# piZero_node_new.net
KiCad netlist of a schematic drawn in EAGLE
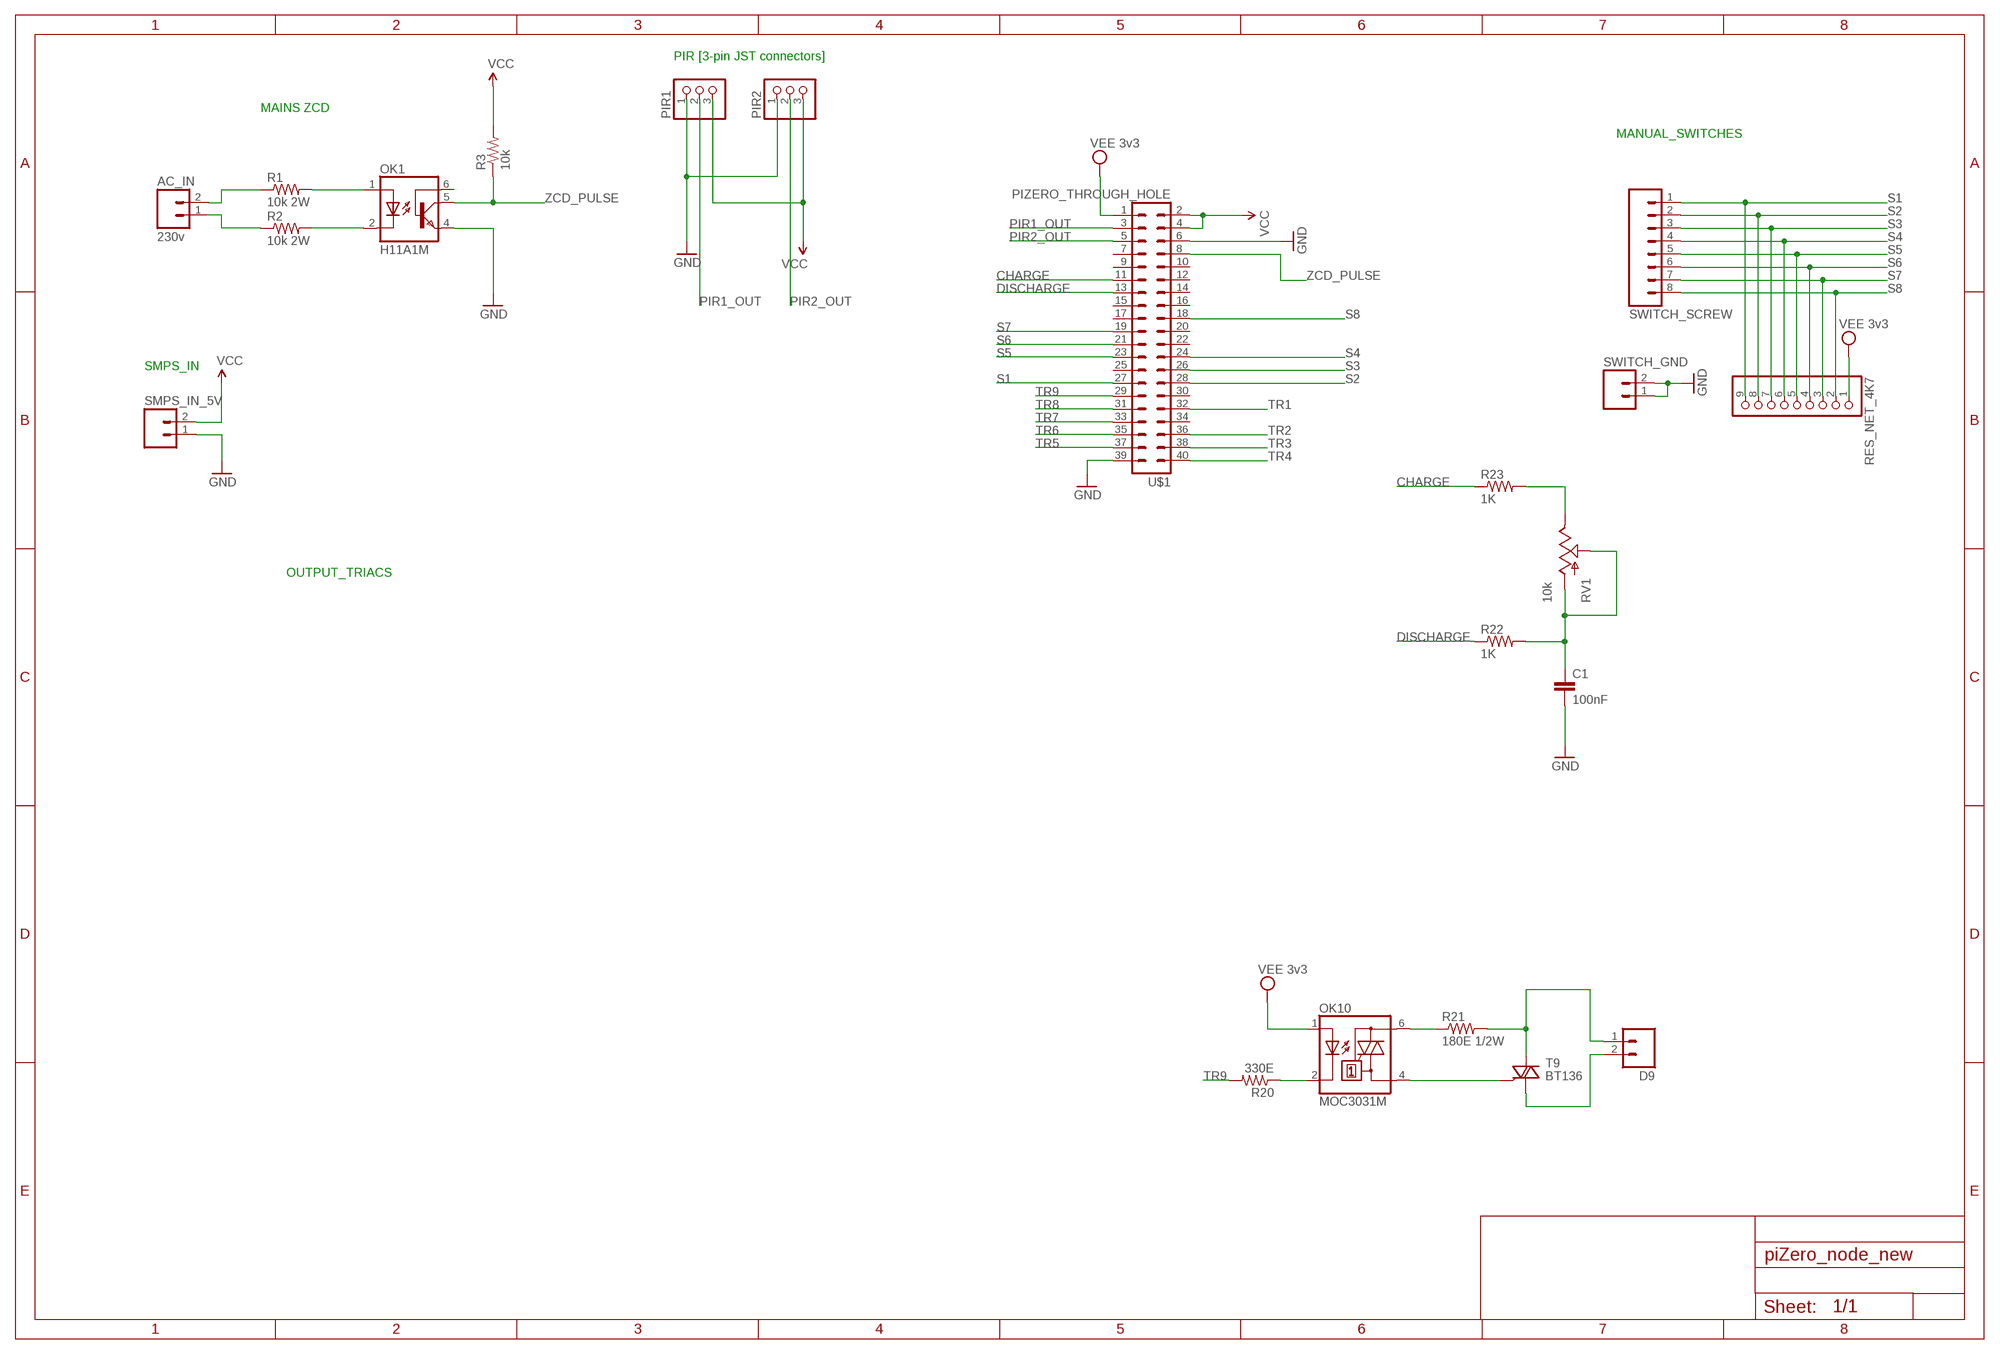
[diagram p0: schematic, sheet 1]

(export (version "E")
  (design (tool "Eeschema 10.0.6"))
  (components
    (comp (ref "AC_IN")
      (value "230v")
      (footprint "eagle-import:SCREWTERMINAL-3.5MM-2_LOCK")
      (libsource (lib "eagle-import") (part "M023.5MM_LOCK"))
    )
    (comp (ref "C1")
      (value "100nF")
      (footprint "eagle-import:C025-025X050")
      (libsource (lib "eagle-import") (part "C-EU025-025X050"))
    )
    (comp (ref "D9")
      (value "M023.5MM_LOCK")
      (footprint "eagle-import:SCREWTERMINAL-3.5MM-2_LOCK")
      (libsource (lib "eagle-import") (part "M023.5MM_LOCK"))
    )
    (comp (ref "OK1")
      (value "H11A1M")
      (footprint "eagle-import:DIL06")
      (fields (field (name "MPN") "H11A1-M"))
      (libsource (lib "eagle-import") (part "H11A?M1"))
    )
    (comp (ref "OK10")
      (value "MOC3031M")
      (footprint "eagle-import:DIL06")
      (fields (field (name "MF") "FAIRCHILD SEMICONDUCTOR"))
      (libsource (lib "eagle-import") (part "MOC3031M"))
    )
    (comp (ref "PIR1")
      (value "PINHD-1X3")
      (footprint "eagle-import:1X03")
      (libsource (lib "eagle-import") (part "PINHD-1X3"))
    )
    (comp (ref "PIR2")
      (value "PINHD-1X3")
      (footprint "eagle-import:1X03")
      (libsource (lib "eagle-import") (part "PINHD-1X3"))
    )
    (comp (ref "R1")
      (value "10k 2W")
      (footprint "eagle-import:AXIAL-0.8")
      (libsource (lib "eagle-import") (part "RESISTORPTH-2W"))
    )
    (comp (ref "R2")
      (value "10k 2W")
      (footprint "eagle-import:AXIAL-0.8")
      (libsource (lib "eagle-import") (part "RESISTORPTH-2W"))
    )
    (comp (ref "R3")
      (value "10k")
      (footprint "eagle-import:AXIAL-0.4")
      (libsource (lib "eagle-import") (part "RESISTORPTH-1/4W"))
    )
    (comp (ref "R20")
      (value "330E")
      (footprint "eagle-import:AXIAL-0.4")
      (libsource (lib "eagle-import") (part "RESISTORPTH-1/4W"))
    )
    (comp (ref "R21")
      (value "180E 1/2W")
      (footprint "eagle-import:AXIAL-0.5")
      (libsource (lib "eagle-import") (part "RESISTORPTH-1/2W"))
    )
    (comp (ref "R22")
      (value "1K")
      (footprint "eagle-import:AXIAL-0.4")
      (libsource (lib "eagle-import") (part "RESISTORPTH-1/4W"))
    )
    (comp (ref "R23")
      (value "1K")
      (footprint "eagle-import:AXIAL-0.4")
      (libsource (lib "eagle-import") (part "RESISTORPTH-1/4W"))
    )
    (comp (ref "RES_NET_4K7")
      (value "PINHD-1X9")
      (footprint "eagle-import:1X09")
      (libsource (lib "eagle-import") (part "PINHD-1X9"))
    )
    (comp (ref "RV1")
      (value "10k")
      (footprint "eagle-import:POT_ALPHA_RV16AF-20")
      (libsource (lib "eagle-import") (part "POT-RV16AF-20"))
    )
    (comp (ref "SMPS_IN_5V")
      (value "M023.5MM_LOCK")
      (footprint "eagle-import:SCREWTERMINAL-3.5MM-2_LOCK")
      (libsource (lib "eagle-import") (part "M023.5MM_LOCK"))
    )
    (comp (ref "SWITCH_GND")
      (value "M023.5MM")
      (footprint "eagle-import:SCREWTERMINAL-3.5MM-2")
      (libsource (lib "eagle-import") (part "M023.5MM"))
    )
    (comp (ref "SWITCH_SCREW")
      (value "M083.5MM-8")
      (footprint "eagle-import:SCREWTERMINAL-3.5MM-8")
      (libsource (lib "eagle-import") (part "M083.5MM-8"))
    )
    (comp (ref "T9")
      (value "BT136")
      (footprint "eagle-import:TO220AB")
      (libsource (lib "eagle-import") (part "BT136"))
    )
    (comp (ref "U$1")
      (value "PIZERO_THROUGH_HOLE")
      (footprint "eagle-import:PIZERO_THOUGH_HOLE")
      (libsource (lib "eagle-import") (part "PIZERO_THROUGH_HOLE"))
    )
  )
  (nets
    (net (code "1") (name "/CHARGE") (class "Default")
      (node (ref "R23") (pin "P$1") (pinfunction "1_P$1") (pintype "passive"))
      (node (ref "U$1") (pin "11") (pinfunction "11_11") (pintype "passive"))
    )
    (net (code "2") (name "/DISCHARGE") (class "Default")
      (node (ref "R22") (pin "P$1") (pinfunction "1_P$1") (pintype "passive"))
      (node (ref "U$1") (pin "13") (pinfunction "13_13") (pintype "passive"))
    )
    (net (code "3") (name "/PIR1_OUT") (class "Default")
      (node (ref "PIR1") (pin "2") (pinfunction "2_2") (pintype "passive"))
      (node (ref "U$1") (pin "3") (pinfunction "3_3") (pintype "passive"))
    )
    (net (code "4") (name "/PIR2_OUT") (class "Default")
      (node (ref "PIR2") (pin "2") (pinfunction "2_2") (pintype "passive"))
      (node (ref "U$1") (pin "5") (pinfunction "5_5") (pintype "passive"))
    )
    (net (code "5") (name "/S1") (class "Default")
      (node (ref "RES_NET_4K7") (pin "9") (pinfunction "9_9") (pintype "passive"))
      (node (ref "SWITCH_SCREW") (pin "1") (pinfunction "1_1") (pintype "passive"))
      (node (ref "U$1") (pin "27") (pinfunction "27_27") (pintype "passive"))
    )
    (net (code "6") (name "/S2") (class "Default")
      (node (ref "RES_NET_4K7") (pin "8") (pinfunction "8_8") (pintype "passive"))
      (node (ref "SWITCH_SCREW") (pin "2") (pinfunction "2_2") (pintype "passive"))
      (node (ref "U$1") (pin "28") (pinfunction "28_28") (pintype "passive"))
    )
    (net (code "7") (name "/S3") (class "Default")
      (node (ref "RES_NET_4K7") (pin "7") (pinfunction "7_7") (pintype "passive"))
      (node (ref "SWITCH_SCREW") (pin "3") (pinfunction "3_3") (pintype "passive"))
      (node (ref "U$1") (pin "26") (pinfunction "26_26") (pintype "passive"))
    )
    (net (code "8") (name "/S4") (class "Default")
      (node (ref "RES_NET_4K7") (pin "6") (pinfunction "6_6") (pintype "passive"))
      (node (ref "SWITCH_SCREW") (pin "4") (pinfunction "4_4") (pintype "passive"))
      (node (ref "U$1") (pin "24") (pinfunction "24_24") (pintype "passive"))
    )
    (net (code "9") (name "/S5") (class "Default")
      (node (ref "RES_NET_4K7") (pin "5") (pinfunction "5_5") (pintype "passive"))
      (node (ref "SWITCH_SCREW") (pin "5") (pinfunction "5_5") (pintype "passive"))
      (node (ref "U$1") (pin "23") (pinfunction "23_23") (pintype "passive"))
    )
    (net (code "10") (name "/S6") (class "Default")
      (node (ref "RES_NET_4K7") (pin "4") (pinfunction "4_4") (pintype "passive"))
      (node (ref "SWITCH_SCREW") (pin "6") (pinfunction "6_6") (pintype "passive"))
      (node (ref "U$1") (pin "21") (pinfunction "21_21") (pintype "passive"))
    )
    (net (code "11") (name "/S7") (class "Default")
      (node (ref "RES_NET_4K7") (pin "3") (pinfunction "3_3") (pintype "passive"))
      (node (ref "SWITCH_SCREW") (pin "7") (pinfunction "7_7") (pintype "passive"))
      (node (ref "U$1") (pin "19") (pinfunction "19_19") (pintype "passive"))
    )
    (net (code "12") (name "/S8") (class "Default")
      (node (ref "RES_NET_4K7") (pin "2") (pinfunction "2_2") (pintype "passive"))
      (node (ref "SWITCH_SCREW") (pin "8") (pinfunction "8_8") (pintype "passive"))
      (node (ref "U$1") (pin "18") (pinfunction "18_18") (pintype "passive"))
    )
    (net (code "13") (name "/TR1") (class "Default")
      (node (ref "U$1") (pin "32") (pinfunction "32_32") (pintype "passive"))
    )
    (net (code "14") (name "/TR2") (class "Default")
      (node (ref "U$1") (pin "36") (pinfunction "36_36") (pintype "passive"))
    )
    (net (code "15") (name "/TR3") (class "Default")
      (node (ref "U$1") (pin "38") (pinfunction "38_38") (pintype "passive"))
    )
    (net (code "16") (name "/TR4") (class "Default")
      (node (ref "U$1") (pin "40") (pinfunction "40_40") (pintype "passive"))
    )
    (net (code "17") (name "/TR5") (class "Default")
      (node (ref "U$1") (pin "37") (pinfunction "37_37") (pintype "passive"))
    )
    (net (code "18") (name "/TR6") (class "Default")
      (node (ref "U$1") (pin "35") (pinfunction "35_35") (pintype "passive"))
    )
    (net (code "19") (name "/TR7") (class "Default")
      (node (ref "U$1") (pin "33") (pinfunction "33_33") (pintype "passive"))
    )
    (net (code "20") (name "/TR8") (class "Default")
      (node (ref "U$1") (pin "31") (pinfunction "31_31") (pintype "passive"))
    )
    (net (code "21") (name "/TR9") (class "Default")
      (node (ref "R20") (pin "P$2") (pinfunction "2_P$2") (pintype "passive"))
      (node (ref "U$1") (pin "29") (pinfunction "29_29") (pintype "passive"))
    )
    (net (code "22") (name "/ZCD_PULSE") (class "Default")
      (node (ref "OK1") (pin "5") (pinfunction "COL_5") (pintype "passive"))
      (node (ref "R3") (pin "P$1") (pinfunction "1_P$1") (pintype "passive"))
      (node (ref "U$1") (pin "8") (pinfunction "8_8") (pintype "passive"))
    )
    (net (code "23") (name "GND") (class "Default")
      (node (ref "C1") (pin "2") (pinfunction "2_2") (pintype "passive"))
      (node (ref "OK1") (pin "4") (pinfunction "EMI_4") (pintype "passive"))
      (node (ref "PIR1") (pin "1") (pinfunction "1_1") (pintype "passive"))
      (node (ref "PIR2") (pin "1") (pinfunction "1_1") (pintype "passive"))
      (node (ref "SMPS_IN_5V") (pin "1") (pinfunction "1_1") (pintype "passive"))
      (node (ref "SWITCH_GND") (pin "1") (pinfunction "1_1") (pintype "passive"))
      (node (ref "SWITCH_GND") (pin "2") (pinfunction "2_2") (pintype "passive"))
      (node (ref "U$1") (pin "39") (pinfunction "39_39") (pintype "passive"))
      (node (ref "U$1") (pin "6") (pinfunction "6_6") (pintype "passive"))
    )
    (net (code "24") (name "Net-(OK1-A)") (class "Default")
      (node (ref "OK1") (pin "1") (pinfunction "A_1") (pintype "passive"))
      (node (ref "R1") (pin "P$2") (pinfunction "2_P$2") (pintype "passive"))
    )
    (net (code "25") (name "Net-(OK1-C)") (class "Default")
      (node (ref "OK1") (pin "2") (pinfunction "C_2") (pintype "passive"))
      (node (ref "R2") (pin "P$2") (pinfunction "2_P$2") (pintype "passive"))
    )
    (net (code "26") (name "Net-(OK10-A1)") (class "Default")
      (node (ref "OK10") (pin "4") (pinfunction "A1_4") (pintype "passive"))
      (node (ref "T9") (pin "3") (pinfunction "G_3") (pintype "passive"))
    )
    (net (code "27") (name "Net-(OK10-A2)") (class "Default")
      (node (ref "OK10") (pin "6") (pinfunction "A2_6") (pintype "passive"))
      (node (ref "R21") (pin "P$1") (pinfunction "1_P$1") (pintype "passive"))
    )
    (net (code "28") (name "Net-(OK10-C)") (class "Default")
      (node (ref "OK10") (pin "2") (pinfunction "C_2") (pintype "passive"))
      (node (ref "R20") (pin "P$1") (pinfunction "1_P$1") (pintype "passive"))
    )
    (net (code "29") (name "Net-(R1-1)") (class "Default")
      (node (ref "AC_IN") (pin "2") (pinfunction "2_2") (pintype "passive"))
      (node (ref "R1") (pin "P$1") (pinfunction "1_P$1") (pintype "passive"))
    )
    (net (code "30") (name "Net-(R2-1)") (class "Default")
      (node (ref "AC_IN") (pin "1") (pinfunction "1_1") (pintype "passive"))
      (node (ref "R2") (pin "P$1") (pinfunction "1_P$1") (pintype "passive"))
    )
    (net (code "31") (name "Net-(R21-2)") (class "Default")
      (node (ref "D9") (pin "1") (pinfunction "1_1") (pintype "passive"))
      (node (ref "R21") (pin "P$2") (pinfunction "2_P$2") (pintype "passive"))
      (node (ref "T9") (pin "2") (pinfunction "A2_2") (pintype "passive"))
    )
    (net (code "32") (name "Net-(R22-2)") (class "Default")
      (node (ref "C1") (pin "1") (pinfunction "1_1") (pintype "passive"))
      (node (ref "R22") (pin "P$2") (pinfunction "2_P$2") (pintype "passive"))
      (node (ref "RV1") (pin "1") (pinfunction "A_1") (pintype "passive"))
      (node (ref "RV1") (pin "2") (pinfunction "S_2") (pintype "passive"))
    )
    (net (code "33") (name "Net-(R23-2)") (class "Default")
      (node (ref "R23") (pin "P$2") (pinfunction "2_P$2") (pintype "passive"))
      (node (ref "RV1") (pin "3") (pinfunction "E_3") (pintype "passive"))
    )
    (net (code "34") (name "Net-(T9-A1)") (class "Default")
      (node (ref "D9") (pin "2") (pinfunction "2_2") (pintype "passive"))
      (node (ref "T9") (pin "1") (pinfunction "A1_1") (pintype "passive"))
    )
    (net (code "35") (name "VCC") (class "Default")
      (node (ref "PIR1") (pin "3") (pinfunction "3_3") (pintype "passive"))
      (node (ref "PIR2") (pin "3") (pinfunction "3_3") (pintype "passive"))
      (node (ref "R3") (pin "P$2") (pinfunction "2_P$2") (pintype "passive"))
      (node (ref "SMPS_IN_5V") (pin "2") (pinfunction "2_2") (pintype "passive"))
      (node (ref "U$1") (pin "2") (pinfunction "2_2") (pintype "passive"))
      (node (ref "U$1") (pin "4") (pinfunction "4_4") (pintype "passive"))
    )
    (net (code "36") (name "VEE 3v3") (class "Default")
      (node (ref "OK10") (pin "1") (pinfunction "A_1") (pintype "passive"))
      (node (ref "RES_NET_4K7") (pin "1") (pinfunction "1_1") (pintype "passive"))
      (node (ref "U$1") (pin "1") (pinfunction "1_1") (pintype "passive"))
    )
    (net (code "37") (name "unconnected-(OK1-BAS-Pad6)") (class "Default")
      (node (ref "OK1") (pin "6") (pinfunction "BAS_6") (pintype "passive"))
    )
    (net (code "38") (name "unconnected-(U$1-Pad7)") (class "Default")
      (node (ref "U$1") (pin "7") (pinfunction "7_7") (pintype "passive"))
    )
    (net (code "39") (name "unconnected-(U$1-Pad9)") (class "Default")
      (node (ref "U$1") (pin "9") (pinfunction "9_9") (pintype "passive"))
    )
    (net (code "40") (name "unconnected-(U$1-Pad10)") (class "Default")
      (node (ref "U$1") (pin "10") (pinfunction "10_10") (pintype "passive"))
    )
    (net (code "41") (name "unconnected-(U$1-Pad12)") (class "Default")
      (node (ref "U$1") (pin "12") (pinfunction "12_12") (pintype "passive"))
    )
    (net (code "42") (name "unconnected-(U$1-Pad14)") (class "Default")
      (node (ref "U$1") (pin "14") (pinfunction "14_14") (pintype "passive"))
    )
    (net (code "43") (name "unconnected-(U$1-Pad15)") (class "Default")
      (node (ref "U$1") (pin "15") (pinfunction "15_15") (pintype "passive"))
    )
    (net (code "44") (name "unconnected-(U$1-Pad16)") (class "Default")
      (node (ref "U$1") (pin "16") (pinfunction "16_16") (pintype "passive"))
    )
    (net (code "45") (name "unconnected-(U$1-Pad17)") (class "Default")
      (node (ref "U$1") (pin "17") (pinfunction "17_17") (pintype "passive"))
    )
    (net (code "46") (name "unconnected-(U$1-Pad20)") (class "Default")
      (node (ref "U$1") (pin "20") (pinfunction "20_20") (pintype "passive"))
    )
    (net (code "47") (name "unconnected-(U$1-Pad22)") (class "Default")
      (node (ref "U$1") (pin "22") (pinfunction "22_22") (pintype "passive"))
    )
    (net (code "48") (name "unconnected-(U$1-Pad25)") (class "Default")
      (node (ref "U$1") (pin "25") (pinfunction "25_25") (pintype "passive"))
    )
    (net (code "49") (name "unconnected-(U$1-Pad30)") (class "Default")
      (node (ref "U$1") (pin "30") (pinfunction "30_30") (pintype "passive"))
    )
    (net (code "50") (name "unconnected-(U$1-Pad34)") (class "Default")
      (node (ref "U$1") (pin "34") (pinfunction "34_34") (pintype "passive"))
    )
  )
)
